# Power_Distribution_5v.net
KiCad netlist of a schematic drawn in EAGLE
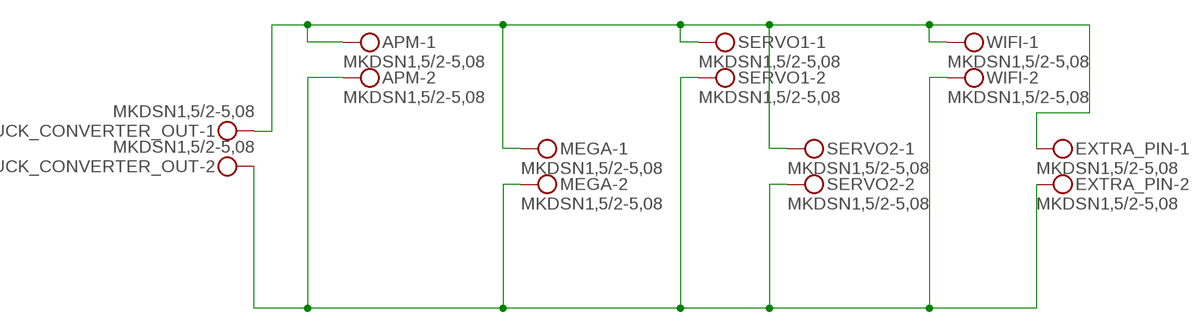
[diagram p0: schematic, sheet 1]

(export (version "E")
  (design (tool "Eeschema 10.0.6"))
  (components
    (comp (ref "APM")
      (value "MKDSN1,5/2-5,08")
      (footprint "eagle-import:MKDSN1,5_2-5,08")
      (libsource (lib "eagle-import") (part "MKDSN1,5/2-5,08"))
    )
    (comp (ref "BUCK_CONVERTER_OUT")
      (value "MKDSN1,5/2-5,08")
      (footprint "eagle-import:MKDSN1,5_2-5,08")
      (libsource (lib "eagle-import") (part "MKDSN1,5/2-5,08"))
    )
    (comp (ref "EXTRA_PIN")
      (value "MKDSN1,5/2-5,08")
      (footprint "eagle-import:MKDSN1,5_2-5,08")
      (libsource (lib "eagle-import") (part "MKDSN1,5/2-5,08"))
    )
    (comp (ref "MEGA")
      (value "MKDSN1,5/2-5,08")
      (footprint "eagle-import:MKDSN1,5_2-5,08")
      (libsource (lib "eagle-import") (part "MKDSN1,5/2-5,08"))
    )
    (comp (ref "SERVO1")
      (value "MKDSN1,5/2-5,08")
      (footprint "eagle-import:MKDSN1,5_2-5,08")
      (libsource (lib "eagle-import") (part "MKDSN1,5/2-5,08"))
    )
    (comp (ref "SERVO2")
      (value "MKDSN1,5/2-5,08")
      (footprint "eagle-import:MKDSN1,5_2-5,08")
      (libsource (lib "eagle-import") (part "MKDSN1,5/2-5,08"))
    )
    (comp (ref "WIFI")
      (value "MKDSN1,5/2-5,08")
      (footprint "eagle-import:MKDSN1,5_2-5,08")
      (libsource (lib "eagle-import") (part "MKDSN1,5/2-5,08"))
    )
  )
  (nets
    (net (code "1") (name "Net-(APMA-KL)") (class "Default")
      (node (ref "APM") (pin "1") (pinfunction "KL_1") (pintype "passive"))
      (node (ref "BUCK_CONVERTER_OUT") (pin "1") (pinfunction "KL_1") (pintype "passive"))
      (node (ref "EXTRA_PIN") (pin "1") (pinfunction "KL_1") (pintype "passive"))
      (node (ref "MEGA") (pin "1") (pinfunction "KL_1") (pintype "passive"))
      (node (ref "SERVO1") (pin "1") (pinfunction "KL_1") (pintype "passive"))
      (node (ref "SERVO2") (pin "1") (pinfunction "KL_1") (pintype "passive"))
      (node (ref "WIFI") (pin "1") (pinfunction "KL_1") (pintype "passive"))
    )
    (net (code "2") (name "Net-(APMB-KL)") (class "Default")
      (node (ref "APM") (pin "2") (pinfunction "KL_2") (pintype "passive"))
      (node (ref "BUCK_CONVERTER_OUT") (pin "2") (pinfunction "KL_2") (pintype "passive"))
      (node (ref "EXTRA_PIN") (pin "2") (pinfunction "KL_2") (pintype "passive"))
      (node (ref "MEGA") (pin "2") (pinfunction "KL_2") (pintype "passive"))
      (node (ref "SERVO1") (pin "2") (pinfunction "KL_2") (pintype "passive"))
      (node (ref "SERVO2") (pin "2") (pinfunction "KL_2") (pintype "passive"))
      (node (ref "WIFI") (pin "2") (pinfunction "KL_2") (pintype "passive"))
    )
  )
)
